# PWR_MGMT.net
KiCad netlist of a schematic drawn in Altium Designer
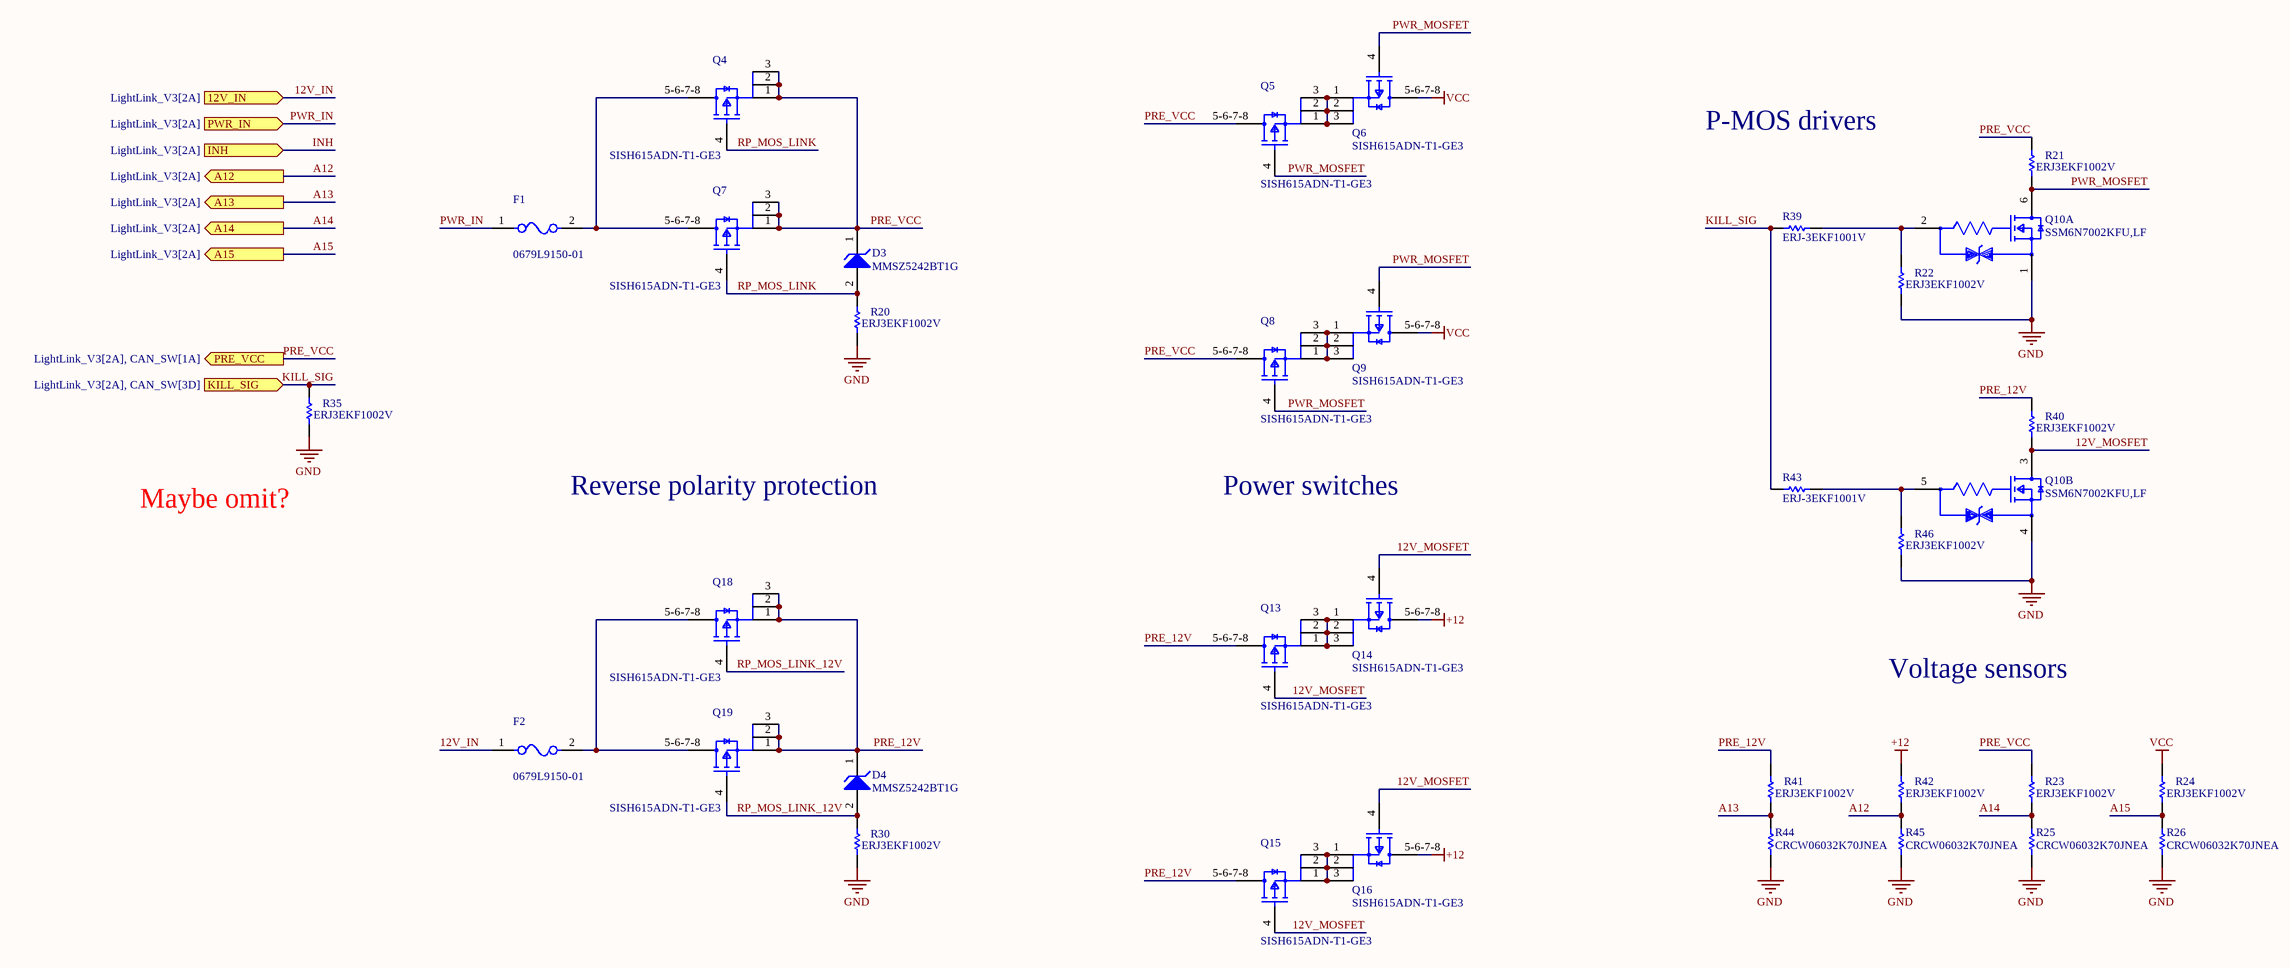
[diagram p0: PWR_MGMT.SchDoc]

(export (version "E")
  (design (tool "Eeschema 10.0.6"))
  (components
    (comp (ref "D3")
      (value "MMSZ5242BT1G")
      (footprint "ONSC-SOD-123-2-425-04_V")
      (description "Zener Voltage Regulator, 500 mW, 2-Pin SOD-123, Pb-Free, Tape and Reel")
      (fields (field (name "MANUFACTURER") "On Semiconductor"))
      (libsource (lib "Altium Content Vault") (part "ONSC-K1A2-2"))
    )
    (comp (ref "D4")
      (value "MMSZ5242BT1G")
      (footprint "ONSC-SOD-123-2-425-04_V")
      (description "Zener Voltage Regulator, 500 mW, 2-Pin SOD-123, Pb-Free, Tape and Reel")
      (fields (field (name "MANUFACTURER") "On Semiconductor"))
      (libsource (lib "Altium Content Vault") (part "ONSC-K1A2-2"))
    )
    (comp (ref "F1")
      (value "0679L9150-01")
      (footprint "FP-0679L-MFG")
      (description "FUSE BRD MNT 15A 125VAC/VDC")
      (fields
        (field (name "OCTOPART") "https://octopart.com/0679l9150-01-bel+fuse-70850665")
        (field (name "MANUFACTURER") "Bel Fuse")
      )
      (libsource (lib "Altium Content Vault") (part "5bcf9b9f640e542cf0359d10258e979"))
    )
    (comp (ref "F2")
      (value "0679L9150-01")
      (footprint "FP-0679L-MFG")
      (description "FUSE BRD MNT 15A 125VAC/VDC")
      (fields
        (field (name "OCTOPART") "https://octopart.com/0679l9150-01-bel+fuse-70850665")
        (field (name "MANUFACTURER") "Bel Fuse")
      )
      (libsource (lib "Altium Content Vault") (part "5bcf9b9f640e542cf0359d10258e979"))
    )
    (comp (ref "Q4")
      (value "SISH615ADN-T1-GE3")
      (footprint "SISH615ADN-T1-GE3-Footprint-1")
      (description "Trans MOSFET P-CH 20V 22.1A 8-Pin PowerPAK 1212 EP T/R")
      (libsource (lib "uORocketry Hardware") (part "SISH615ADN-T1-GE3-Symbol-1"))
    )
    (comp (ref "Q5")
      (value "SISH615ADN-T1-GE3")
      (footprint "SISH615ADN-T1-GE3-Footprint-1")
      (description "Trans MOSFET P-CH 20V 22.1A 8-Pin PowerPAK 1212 EP T/R")
      (libsource (lib "uORocketry Hardware") (part "SISH615ADN-T1-GE3-Symbol-1"))
    )
    (comp (ref "Q6")
      (value "SISH615ADN-T1-GE3")
      (footprint "SISH615ADN-T1-GE3-Footprint-1")
      (description "Trans MOSFET P-CH 20V 22.1A 8-Pin PowerPAK 1212 EP T/R")
      (libsource (lib "uORocketry Hardware") (part "SISH615ADN-T1-GE3-Symbol-1"))
    )
    (comp (ref "Q7")
      (value "SISH615ADN-T1-GE3")
      (footprint "SISH615ADN-T1-GE3-Footprint-1")
      (description "Trans MOSFET P-CH 20V 22.1A 8-Pin PowerPAK 1212 EP T/R")
      (libsource (lib "uORocketry Hardware") (part "SISH615ADN-T1-GE3-Symbol-1"))
    )
    (comp (ref "Q8")
      (value "SISH615ADN-T1-GE3")
      (footprint "SISH615ADN-T1-GE3-Footprint-1")
      (description "Trans MOSFET P-CH 20V 22.1A 8-Pin PowerPAK 1212 EP T/R")
      (libsource (lib "uORocketry Hardware") (part "SISH615ADN-T1-GE3-Symbol-1"))
    )
    (comp (ref "Q9")
      (value "SISH615ADN-T1-GE3")
      (footprint "SISH615ADN-T1-GE3-Footprint-1")
      (description "Trans MOSFET P-CH 20V 22.1A 8-Pin PowerPAK 1212 EP T/R")
      (libsource (lib "uORocketry Hardware") (part "SISH615ADN-T1-GE3-Symbol-1"))
    )
    (comp (ref "Q10")
      (value "SSM6N7002KFU,LF")
      (footprint "FP-SSOP6-P-0_65A-MFG")
      (description "MOSFET 2N-CH 60V 0.3A")
      (libsource (lib "Altium Content Vault") (part "088aa6ac103fdeebe0d1c52ece6b7b9"))
    )
    (comp (ref "Q13")
      (value "SISH615ADN-T1-GE3")
      (footprint "SISH615ADN-T1-GE3-Footprint-1")
      (description "Trans MOSFET P-CH 20V 22.1A 8-Pin PowerPAK 1212 EP T/R")
      (libsource (lib "uORocketry Hardware") (part "SISH615ADN-T1-GE3-Symbol-1"))
    )
    (comp (ref "Q14")
      (value "SISH615ADN-T1-GE3")
      (footprint "SISH615ADN-T1-GE3-Footprint-1")
      (description "Trans MOSFET P-CH 20V 22.1A 8-Pin PowerPAK 1212 EP T/R")
      (libsource (lib "uORocketry Hardware") (part "SISH615ADN-T1-GE3-Symbol-1"))
    )
    (comp (ref "Q15")
      (value "SISH615ADN-T1-GE3")
      (footprint "SISH615ADN-T1-GE3-Footprint-1")
      (description "Trans MOSFET P-CH 20V 22.1A 8-Pin PowerPAK 1212 EP T/R")
      (libsource (lib "uORocketry Hardware") (part "SISH615ADN-T1-GE3-Symbol-1"))
    )
    (comp (ref "Q16")
      (value "SISH615ADN-T1-GE3")
      (footprint "SISH615ADN-T1-GE3-Footprint-1")
      (description "Trans MOSFET P-CH 20V 22.1A 8-Pin PowerPAK 1212 EP T/R")
      (libsource (lib "uORocketry Hardware") (part "SISH615ADN-T1-GE3-Symbol-1"))
    )
    (comp (ref "Q18")
      (value "SISH615ADN-T1-GE3")
      (footprint "SISH615ADN-T1-GE3-Footprint-1")
      (description "Trans MOSFET P-CH 20V 22.1A 8-Pin PowerPAK 1212 EP T/R")
      (libsource (lib "uORocketry Hardware") (part "SISH615ADN-T1-GE3-Symbol-1"))
    )
    (comp (ref "Q19")
      (value "SISH615ADN-T1-GE3")
      (footprint "SISH615ADN-T1-GE3-Footprint-1")
      (description "Trans MOSFET P-CH 20V 22.1A 8-Pin PowerPAK 1212 EP T/R")
      (libsource (lib "uORocketry Hardware") (part "SISH615ADN-T1-GE3-Symbol-1"))
    )
    (comp (ref "R20")
      (value "ERJ3EKF1002V")
      (footprint "RESC1609X55X30LL15T15")
      (description "Chip Resistor, 10 KOhm, +/- 1%, 0.1 W, -55 to 155 degC, 0603 (1608 Metric), RoHS, Tape and Reel")
      (fields (field (name "TOLERANCE") "1%") (field (name "MANUFACTURER") "Panasonic"))
      (libsource (lib "Altium Content Vault") (part "RES-2"))
    )
    (comp (ref "R21")
      (value "ERJ3EKF1002V")
      (footprint "RESC1609X55X30LL15T15")
      (description "Chip Resistor, 10 KOhm, +/- 1%, 0.1 W, -55 to 155 degC, 0603 (1608 Metric), RoHS, Tape and Reel")
      (fields (field (name "TOLERANCE") "1%") (field (name "MANUFACTURER") "Panasonic"))
      (libsource (lib "Altium Content Vault") (part "RES-2"))
    )
    (comp (ref "R22")
      (value "ERJ3EKF1002V")
      (footprint "RESC1609X55X30LL15T15")
      (description "Chip Resistor, 10 KOhm, +/- 1%, 0.1 W, -55 to 155 degC, 0603 (1608 Metric), RoHS, Tape and Reel")
      (fields (field (name "TOLERANCE") "1%") (field (name "MANUFACTURER") "Panasonic"))
      (libsource (lib "Altium Content Vault") (part "RES-2"))
    )
    (comp (ref "R23")
      (value "ERJ3EKF1002V")
      (footprint "RESC1609X55X30LL15T15")
      (description "Chip Resistor, 10 KOhm, +/- 1%, 0.1 W, -55 to 155 degC, 0603 (1608 Metric), RoHS, Tape and Reel")
      (fields (field (name "TOLERANCE") "1%") (field (name "MANUFACTURER") "Panasonic"))
      (libsource (lib "Altium Content Vault") (part "RES-2"))
    )
    (comp (ref "R24")
      (value "ERJ3EKF1002V")
      (footprint "RESC1609X55X30LL15T15")
      (description "Chip Resistor, 10 KOhm, +/- 1%, 0.1 W, -55 to 155 degC, 0603 (1608 Metric), RoHS, Tape and Reel")
      (fields (field (name "TOLERANCE") "1%") (field (name "MANUFACTURER") "Panasonic"))
      (libsource (lib "Altium Content Vault") (part "RES-2"))
    )
    (comp (ref "R25")
      (value "CRCW06032K70JNEA")
      (footprint "RESC1609X50X30ML10T20")
      (fields (field (name "MANUFACTURER") "Vishay Dale"))
      (libsource (lib "Altium Content Vault") (part "RES"))
    )
    (comp (ref "R26")
      (value "CRCW06032K70JNEA")
      (footprint "RESC1609X50X30ML10T20")
      (fields (field (name "MANUFACTURER") "Vishay Dale"))
      (libsource (lib "Altium Content Vault") (part "RES"))
    )
    (comp (ref "R30")
      (value "ERJ3EKF1002V")
      (footprint "RESC1609X55X30LL15T15")
      (description "Chip Resistor, 10 KOhm, +/- 1%, 0.1 W, -55 to 155 degC, 0603 (1608 Metric), RoHS, Tape and Reel")
      (fields (field (name "TOLERANCE") "1%") (field (name "MANUFACTURER") "Panasonic"))
      (libsource (lib "Altium Content Vault") (part "RES-2"))
    )
    (comp (ref "R35")
      (value "ERJ3EKF1002V")
      (footprint "RESC1609X55X30LL15T15")
      (description "Chip Resistor, 10 KOhm, +/- 1%, 0.1 W, -55 to 155 degC, 0603 (1608 Metric), RoHS, Tape and Reel")
      (fields (field (name "TOLERANCE") "1%") (field (name "MANUFACTURER") "Panasonic"))
      (libsource (lib "Altium Content Vault") (part "RES-2"))
    )
    (comp (ref "R39")
      (value "ERJ-3EKF1001V")
      (footprint "RESC1608X55X30LL15T15")
      (fields (field (name "MANUFACTURER") "Panasonic"))
      (libsource (lib "Altium Content Vault") (part "RES"))
    )
    (comp (ref "R40")
      (value "ERJ3EKF1002V")
      (footprint "RESC1609X55X30LL15T15")
      (description "Chip Resistor, 10 KOhm, +/- 1%, 0.1 W, -55 to 155 degC, 0603 (1608 Metric), RoHS, Tape and Reel")
      (fields (field (name "TOLERANCE") "1%") (field (name "MANUFACTURER") "Panasonic"))
      (libsource (lib "Altium Content Vault") (part "RES-2"))
    )
    (comp (ref "R41")
      (value "ERJ3EKF1002V")
      (footprint "RESC1609X55X30LL15T15")
      (description "Chip Resistor, 10 KOhm, +/- 1%, 0.1 W, -55 to 155 degC, 0603 (1608 Metric), RoHS, Tape and Reel")
      (fields (field (name "TOLERANCE") "1%") (field (name "MANUFACTURER") "Panasonic"))
      (libsource (lib "Altium Content Vault") (part "RES-2"))
    )
    (comp (ref "R42")
      (value "ERJ3EKF1002V")
      (footprint "RESC1609X55X30LL15T15")
      (description "Chip Resistor, 10 KOhm, +/- 1%, 0.1 W, -55 to 155 degC, 0603 (1608 Metric), RoHS, Tape and Reel")
      (fields (field (name "TOLERANCE") "1%") (field (name "MANUFACTURER") "Panasonic"))
      (libsource (lib "Altium Content Vault") (part "RES-2"))
    )
    (comp (ref "R43")
      (value "ERJ-3EKF1001V")
      (footprint "RESC1608X55X30LL15T15")
      (fields (field (name "MANUFACTURER") "Panasonic"))
      (libsource (lib "Altium Content Vault") (part "RES"))
    )
    (comp (ref "R44")
      (value "CRCW06032K70JNEA")
      (footprint "RESC1609X50X30ML10T20")
      (fields (field (name "MANUFACTURER") "Vishay Dale"))
      (libsource (lib "Altium Content Vault") (part "RES"))
    )
    (comp (ref "R45")
      (value "CRCW06032K70JNEA")
      (footprint "RESC1609X50X30ML10T20")
      (fields (field (name "MANUFACTURER") "Vishay Dale"))
      (libsource (lib "Altium Content Vault") (part "RES"))
    )
    (comp (ref "R46")
      (value "ERJ3EKF1002V")
      (footprint "RESC1609X55X30LL15T15")
      (description "Chip Resistor, 10 KOhm, +/- 1%, 0.1 W, -55 to 155 degC, 0603 (1608 Metric), RoHS, Tape and Reel")
      (fields (field (name "TOLERANCE") "1%") (field (name "MANUFACTURER") "Panasonic"))
      (libsource (lib "Altium Content Vault") (part "RES-2"))
    )
  )
  (nets
    (net (code "1") (name "+12") (class "Default")
      (node (ref "Q14") (pin "5-6-7-8") (pinfunction "D_5-6-7-8") (pintype "passive"))
      (node (ref "Q16") (pin "5-6-7-8") (pinfunction "D_5-6-7-8") (pintype "passive"))
      (node (ref "R42") (pin "1") (pinfunction "1_1") (pintype "passive"))
    )
    (net (code "2") (name "/12V_IN") (class "Default")
      (node (ref "F2") (pin "1") (pinfunction "1_1") (pintype "passive"))
    )
    (net (code "3") (name "/12V_MOSFET") (class "Default")
      (node (ref "Q10") (pin "3") (pinfunction "Drain2_3") (pintype "passive"))
      (node (ref "Q13") (pin "4") (pinfunction "G_4") (pintype "passive"))
      (node (ref "Q14") (pin "4") (pinfunction "G_4") (pintype "passive"))
      (node (ref "Q15") (pin "4") (pinfunction "G_4") (pintype "passive"))
      (node (ref "Q16") (pin "4") (pinfunction "G_4") (pintype "passive"))
      (node (ref "R40") (pin "2") (pinfunction "2_2") (pintype "passive"))
    )
    (net (code "4") (name "/A12") (class "Default")
      (node (ref "R42") (pin "2") (pinfunction "2_2") (pintype "passive"))
      (node (ref "R45") (pin "2") (pinfunction "2_2") (pintype "passive"))
    )
    (net (code "5") (name "/A13") (class "Default")
      (node (ref "R41") (pin "2") (pinfunction "2_2") (pintype "passive"))
      (node (ref "R44") (pin "2") (pinfunction "2_2") (pintype "passive"))
    )
    (net (code "6") (name "/A14") (class "Default")
      (node (ref "R23") (pin "2") (pinfunction "2_2") (pintype "passive"))
      (node (ref "R25") (pin "2") (pinfunction "2_2") (pintype "passive"))
    )
    (net (code "7") (name "/A15") (class "Default")
      (node (ref "R24") (pin "2") (pinfunction "2_2") (pintype "passive"))
      (node (ref "R26") (pin "2") (pinfunction "2_2") (pintype "passive"))
    )
    (net (code "9") (name "/KILL_SIG") (class "Default")
      (node (ref "R35") (pin "1") (pinfunction "1_1") (pintype "passive"))
      (node (ref "R39") (pin "1") (pinfunction "1_1") (pintype "passive"))
      (node (ref "R43") (pin "1") (pinfunction "1_1") (pintype "passive"))
    )
    (net (code "10") (name "/PRE_12V") (class "Default")
      (node (ref "D4") (pin "1") (pinfunction "K_1") (pintype "passive"))
      (node (ref "Q13") (pin "5-6-7-8") (pinfunction "D_5-6-7-8") (pintype "passive"))
      (node (ref "Q15") (pin "5-6-7-8") (pinfunction "D_5-6-7-8") (pintype "passive"))
      (node (ref "Q18") (pin "1") (pinfunction "S_1") (pintype "passive"))
      (node (ref "Q18") (pin "2") (pinfunction "S_2") (pintype "passive"))
      (node (ref "Q18") (pin "3") (pinfunction "S_3") (pintype "passive"))
      (node (ref "Q19") (pin "1") (pinfunction "S_1") (pintype "passive"))
      (node (ref "Q19") (pin "2") (pinfunction "S_2") (pintype "passive"))
      (node (ref "Q19") (pin "3") (pinfunction "S_3") (pintype "passive"))
      (node (ref "R40") (pin "1") (pinfunction "1_1") (pintype "passive"))
      (node (ref "R41") (pin "1") (pinfunction "1_1") (pintype "passive"))
    )
    (net (code "11") (name "/PRE_VCC") (class "Default")
      (node (ref "D3") (pin "1") (pinfunction "K_1") (pintype "passive"))
      (node (ref "Q4") (pin "1") (pinfunction "S_1") (pintype "passive"))
      (node (ref "Q4") (pin "2") (pinfunction "S_2") (pintype "passive"))
      (node (ref "Q4") (pin "3") (pinfunction "S_3") (pintype "passive"))
      (node (ref "Q5") (pin "5-6-7-8") (pinfunction "D_5-6-7-8") (pintype "passive"))
      (node (ref "Q7") (pin "1") (pinfunction "S_1") (pintype "passive"))
      (node (ref "Q7") (pin "2") (pinfunction "S_2") (pintype "passive"))
      (node (ref "Q7") (pin "3") (pinfunction "S_3") (pintype "passive"))
      (node (ref "Q8") (pin "5-6-7-8") (pinfunction "D_5-6-7-8") (pintype "passive"))
      (node (ref "R21") (pin "1") (pinfunction "1_1") (pintype "passive"))
      (node (ref "R23") (pin "1") (pinfunction "1_1") (pintype "passive"))
    )
    (net (code "12") (name "/PWR_IN") (class "Default")
      (node (ref "F1") (pin "1") (pinfunction "1_1") (pintype "passive"))
    )
    (net (code "13") (name "/PWR_MOSFET") (class "Default")
      (node (ref "Q10") (pin "6") (pinfunction "Drain1_6") (pintype "passive"))
      (node (ref "Q5") (pin "4") (pinfunction "G_4") (pintype "passive"))
      (node (ref "Q6") (pin "4") (pinfunction "G_4") (pintype "passive"))
      (node (ref "Q8") (pin "4") (pinfunction "G_4") (pintype "passive"))
      (node (ref "Q9") (pin "4") (pinfunction "G_4") (pintype "passive"))
      (node (ref "R21") (pin "2") (pinfunction "2_2") (pintype "passive"))
    )
    (net (code "14") (name "/RP_MOS_LINK") (class "Default")
      (node (ref "D3") (pin "2") (pinfunction "A_2") (pintype "passive"))
      (node (ref "Q4") (pin "4") (pinfunction "G_4") (pintype "passive"))
      (node (ref "Q7") (pin "4") (pinfunction "G_4") (pintype "passive"))
      (node (ref "R20") (pin "1") (pinfunction "1_1") (pintype "passive"))
    )
    (net (code "15") (name "/RP_MOS_LINK_12V") (class "Default")
      (node (ref "D4") (pin "2") (pinfunction "A_2") (pintype "passive"))
      (node (ref "Q18") (pin "4") (pinfunction "G_4") (pintype "passive"))
      (node (ref "Q19") (pin "4") (pinfunction "G_4") (pintype "passive"))
      (node (ref "R30") (pin "1") (pinfunction "1_1") (pintype "passive"))
    )
    (net (code "16") (name "GND") (class "Default")
      (node (ref "Q10") (pin "1") (pinfunction "Source1_1") (pintype "passive"))
      (node (ref "Q10") (pin "4") (pinfunction "Source2_4") (pintype "passive"))
      (node (ref "R20") (pin "2") (pinfunction "2_2") (pintype "passive"))
      (node (ref "R22") (pin "2") (pinfunction "2_2") (pintype "passive"))
      (node (ref "R25") (pin "1") (pinfunction "1_1") (pintype "passive"))
      (node (ref "R26") (pin "1") (pinfunction "1_1") (pintype "passive"))
      (node (ref "R30") (pin "2") (pinfunction "2_2") (pintype "passive"))
      (node (ref "R35") (pin "2") (pinfunction "2_2") (pintype "passive"))
      (node (ref "R44") (pin "1") (pinfunction "1_1") (pintype "passive"))
      (node (ref "R45") (pin "1") (pinfunction "1_1") (pintype "passive"))
      (node (ref "R46") (pin "2") (pinfunction "2_2") (pintype "passive"))
    )
    (net (code "17") (name "Net-(Q4-D)") (class "Default")
      (node (ref "F1") (pin "2") (pinfunction "2_2") (pintype "passive"))
      (node (ref "Q4") (pin "5-6-7-8") (pinfunction "D_5-6-7-8") (pintype "passive"))
      (node (ref "Q7") (pin "5-6-7-8") (pinfunction "D_5-6-7-8") (pintype "passive"))
    )
    (net (code "18") (name "Net-(Q5-S-Pad1)") (class "Default")
      (node (ref "Q5") (pin "1") (pinfunction "S_1") (pintype "passive"))
      (node (ref "Q5") (pin "2") (pinfunction "S_2") (pintype "passive"))
      (node (ref "Q5") (pin "3") (pinfunction "S_3") (pintype "passive"))
      (node (ref "Q6") (pin "1") (pinfunction "S_1") (pintype "passive"))
      (node (ref "Q6") (pin "2") (pinfunction "S_2") (pintype "passive"))
      (node (ref "Q6") (pin "3") (pinfunction "S_3") (pintype "passive"))
    )
    (net (code "19") (name "Net-(Q8-S-Pad1)") (class "Default")
      (node (ref "Q8") (pin "1") (pinfunction "S_1") (pintype "passive"))
      (node (ref "Q8") (pin "2") (pinfunction "S_2") (pintype "passive"))
      (node (ref "Q8") (pin "3") (pinfunction "S_3") (pintype "passive"))
      (node (ref "Q9") (pin "1") (pinfunction "S_1") (pintype "passive"))
      (node (ref "Q9") (pin "2") (pinfunction "S_2") (pintype "passive"))
      (node (ref "Q9") (pin "3") (pinfunction "S_3") (pintype "passive"))
    )
    (net (code "20") (name "Net-(Q10A-Gate1)") (class "Default")
      (node (ref "Q10") (pin "2") (pinfunction "Gate1_2") (pintype "passive"))
      (node (ref "R22") (pin "1") (pinfunction "1_1") (pintype "passive"))
      (node (ref "R39") (pin "2") (pinfunction "2_2") (pintype "passive"))
    )
    (net (code "21") (name "Net-(Q10B-Gate2)") (class "Default")
      (node (ref "Q10") (pin "5") (pinfunction "Gate2_5") (pintype "passive"))
      (node (ref "R43") (pin "2") (pinfunction "2_2") (pintype "passive"))
      (node (ref "R46") (pin "1") (pinfunction "1_1") (pintype "passive"))
    )
    (net (code "22") (name "Net-(Q13-S-Pad1)") (class "Default")
      (node (ref "Q13") (pin "1") (pinfunction "S_1") (pintype "passive"))
      (node (ref "Q13") (pin "2") (pinfunction "S_2") (pintype "passive"))
      (node (ref "Q13") (pin "3") (pinfunction "S_3") (pintype "passive"))
      (node (ref "Q14") (pin "1") (pinfunction "S_1") (pintype "passive"))
      (node (ref "Q14") (pin "2") (pinfunction "S_2") (pintype "passive"))
      (node (ref "Q14") (pin "3") (pinfunction "S_3") (pintype "passive"))
    )
    (net (code "23") (name "Net-(Q15-S-Pad1)") (class "Default")
      (node (ref "Q15") (pin "1") (pinfunction "S_1") (pintype "passive"))
      (node (ref "Q15") (pin "2") (pinfunction "S_2") (pintype "passive"))
      (node (ref "Q15") (pin "3") (pinfunction "S_3") (pintype "passive"))
      (node (ref "Q16") (pin "1") (pinfunction "S_1") (pintype "passive"))
      (node (ref "Q16") (pin "2") (pinfunction "S_2") (pintype "passive"))
      (node (ref "Q16") (pin "3") (pinfunction "S_3") (pintype "passive"))
    )
    (net (code "24") (name "Net-(Q18-D)") (class "Default")
      (node (ref "F2") (pin "2") (pinfunction "2_2") (pintype "passive"))
      (node (ref "Q18") (pin "5-6-7-8") (pinfunction "D_5-6-7-8") (pintype "passive"))
      (node (ref "Q19") (pin "5-6-7-8") (pinfunction "D_5-6-7-8") (pintype "passive"))
    )
    (net (code "25") (name "VCC") (class "Default")
      (node (ref "Q6") (pin "5-6-7-8") (pinfunction "D_5-6-7-8") (pintype "passive"))
      (node (ref "Q9") (pin "5-6-7-8") (pinfunction "D_5-6-7-8") (pintype "passive"))
      (node (ref "R24") (pin "1") (pinfunction "1_1") (pintype "passive"))
    )
  )
)
